# SparkFun_Pi_AVR_Programmer_HAT.net
KiCad netlist of a schematic drawn in EAGLE
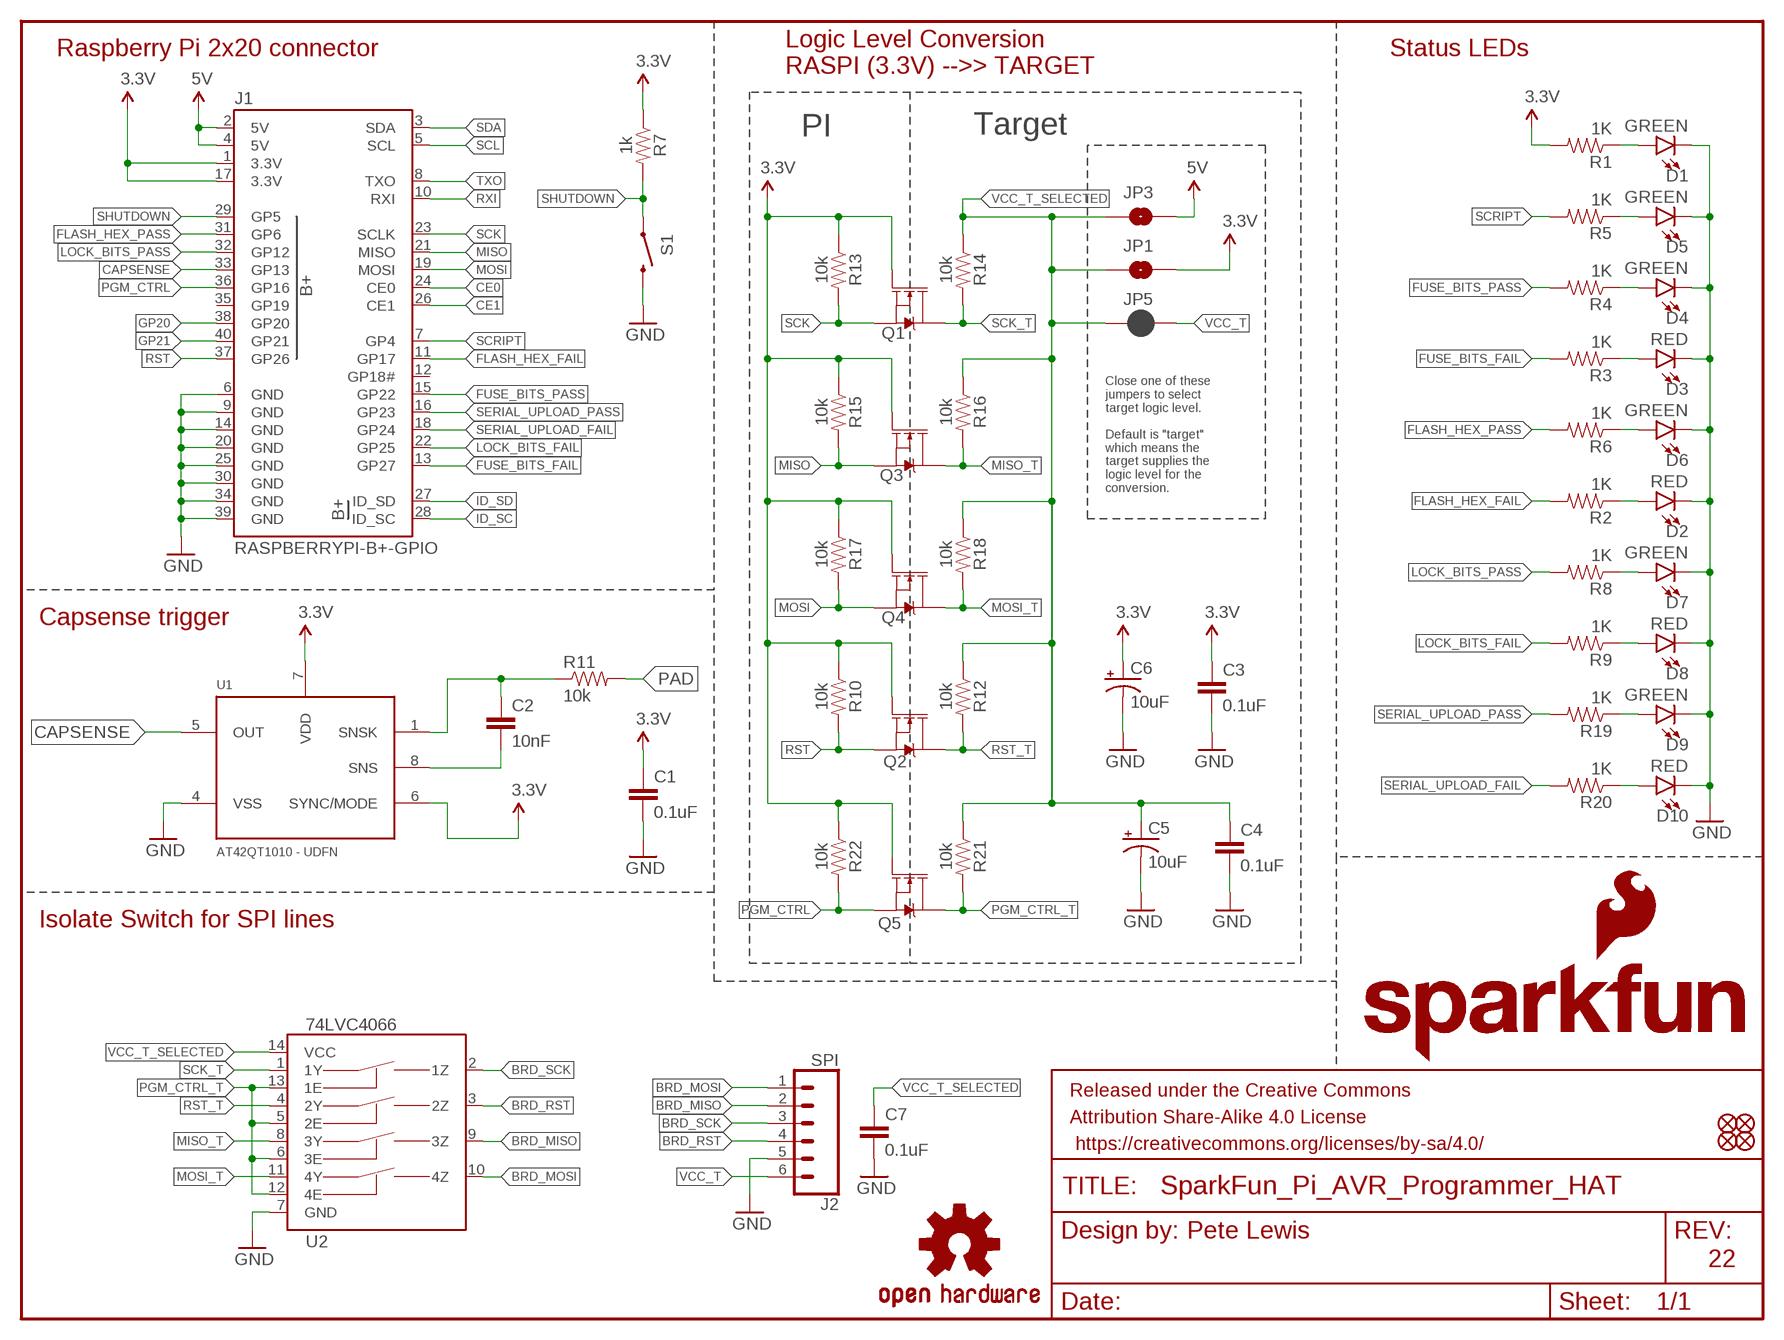
[diagram p0: schematic, sheet 1]

(export (version "E")
  (design (tool "Eeschema 10.0.6"))
  (components
    (comp (ref "C1")
      (value "0.1uF")
      (footprint "eagle-import:0603-CAP")
      (libsource (lib "eagle-import") (part "0.1UF-25V(+80/-20%)(0603)"))
    )
    (comp (ref "C2")
      (value "10nF")
      (footprint "eagle-import:0603-CAP")
      (libsource (lib "eagle-import") (part "10NF/10000PF-50V-10%(0603)"))
    )
    (comp (ref "C3")
      (value "0.1uF")
      (footprint "eagle-import:0603")
      (libsource (lib "eagle-import") (part "0.1UF-0603-25V-(+80/-20%)"))
    )
    (comp (ref "C4")
      (value "0.1uF")
      (footprint "eagle-import:0603")
      (libsource (lib "eagle-import") (part "0.1UF-0603-25V-(+80/-20%)"))
    )
    (comp (ref "C5")
      (value "10uF")
      (footprint "eagle-import:EIA3216")
      (libsource (lib "eagle-import") (part "10UF-POLAR-EIA3216-16V-10%(TANT)"))
    )
    (comp (ref "C6")
      (value "10uF")
      (footprint "eagle-import:EIA3216")
      (libsource (lib "eagle-import") (part "10UF-POLAR-EIA3216-16V-10%(TANT)"))
    )
    (comp (ref "C7")
      (value "0.1uF")
      (footprint "eagle-import:0603")
      (libsource (lib "eagle-import") (part "0.1UF-0603-25V-(+80/-20%)"))
    )
    (comp (ref "D1")
      (value "GREEN")
      (footprint "eagle-import:LED-1206")
      (libsource (lib "eagle-import") (part "LED-GREEN1206"))
    )
    (comp (ref "D2")
      (value "RED")
      (footprint "eagle-import:LED-1206")
      (libsource (lib "eagle-import") (part "LED-RED1206"))
    )
    (comp (ref "D3")
      (value "RED")
      (footprint "eagle-import:LED-1206")
      (libsource (lib "eagle-import") (part "LED-RED1206"))
    )
    (comp (ref "D4")
      (value "GREEN")
      (footprint "eagle-import:LED-1206")
      (libsource (lib "eagle-import") (part "LED-GREEN1206"))
    )
    (comp (ref "D5")
      (value "GREEN")
      (footprint "eagle-import:LED-1206")
      (libsource (lib "eagle-import") (part "LED-GREEN1206"))
    )
    (comp (ref "D6")
      (value "GREEN")
      (footprint "eagle-import:LED-1206")
      (libsource (lib "eagle-import") (part "LED-GREEN1206"))
    )
    (comp (ref "D7")
      (value "GREEN")
      (footprint "eagle-import:LED-1206")
      (libsource (lib "eagle-import") (part "LED-GREEN1206"))
    )
    (comp (ref "D8")
      (value "RED")
      (footprint "eagle-import:LED-1206")
      (libsource (lib "eagle-import") (part "LED-RED1206"))
    )
    (comp (ref "D9")
      (value "GREEN")
      (footprint "eagle-import:LED-1206")
      (libsource (lib "eagle-import") (part "LED-GREEN1206"))
    )
    (comp (ref "D10")
      (value "RED")
      (footprint "eagle-import:LED-1206")
      (libsource (lib "eagle-import") (part "LED-RED1206"))
    )
    (comp (ref "FD1")
      (value "FIDUCIALUFIDUCIAL")
      (footprint "eagle-import:FIDUCIAL-MICRO")
      (libsource (lib "eagle-import") (part "FIDUCIALUFIDUCIAL"))
    )
    (comp (ref "FD2")
      (value "FIDUCIALUFIDUCIAL")
      (footprint "eagle-import:FIDUCIAL-MICRO")
      (libsource (lib "eagle-import") (part "FIDUCIALUFIDUCIAL"))
    )
    (comp (ref "FD3")
      (value "FIDUCIALUFIDUCIAL")
      (footprint "eagle-import:FIDUCIAL-MICRO")
      (libsource (lib "eagle-import") (part "FIDUCIALUFIDUCIAL"))
    )
    (comp (ref "FD4")
      (value "FIDUCIALUFIDUCIAL")
      (footprint "eagle-import:FIDUCIAL-MICRO")
      (libsource (lib "eagle-import") (part "FIDUCIALUFIDUCIAL"))
    )
    (comp (ref "FRAME1")
      (value "FRAME-LETTER")
      (footprint "eagle-import:CREATIVE_COMMONS")
      (libsource (lib "eagle-import") (part "FRAME-LETTER"))
    )
    (comp (ref "J1")
      (value "RASPBERRYPI-B+-GPIO")
      (footprint "eagle-import:2X20-SHROUDED")
      (libsource (lib "eagle-import") (part "RASPBERRYPI-B+-GPIO"))
    )
    (comp (ref "J2")
      (value "SPI")
      (footprint "eagle-import:1X06-SMD_RA_MALE")
      (libsource (lib "eagle-import") (part "CONN_06SMD"))
    )
    (comp (ref "JP1")
      (value "JUMPER-SMT_2_NO_SILK")
      (footprint "eagle-import:SMT-JUMPER_2_NO_SILK")
      (libsource (lib "eagle-import") (part "JUMPER-SMT_2_NO_SILK"))
    )
    (comp (ref "JP3")
      (value "JUMPER-SMT_2_NO_SILK")
      (footprint "eagle-import:SMT-JUMPER_2_NO_SILK")
      (libsource (lib "eagle-import") (part "JUMPER-SMT_2_NO_SILK"))
    )
    (comp (ref "JP5")
      (value "JUMPER-SMT_2_NC_PASTE_SILK")
      (footprint "eagle-import:SMT-JUMPER_2_NC_PASTE_SILK")
      (libsource (lib "eagle-import") (part "JUMPER-SMT_2_NC_PASTE_SILK"))
    )
    (comp (ref "LOGO1")
      (value "SFE_LOGO_FLAME.2_INCH")
      (footprint "eagle-import:SFE_LOGO_FLAME_.2")
      (libsource (lib "eagle-import") (part "SFE_LOGO_FLAME.2_INCH"))
    )
    (comp (ref "LOGO2")
      (value "OSHW-LOGOL")
      (footprint "eagle-import:OSHW-LOGO-L")
      (libsource (lib "eagle-import") (part "OSHW-LOGOL"))
    )
    (comp (ref "LOGO3")
      (value "SFE_LOGO_NAME.6_INCH")
      (footprint "eagle-import:SFE_LOGO_NAME_.6")
      (libsource (lib "eagle-import") (part "SFE_LOGO_NAME.6_INCH"))
    )
    (comp (ref "Q1")
      (value "220mA/50V/3.5Ω")
      (footprint "eagle-import:SOT23-3")
      (libsource (lib "eagle-import") (part "MOSFET-NCH-BSS138"))
    )
    (comp (ref "Q2")
      (value "220mA/50V/3.5Ω")
      (footprint "eagle-import:SOT23-3")
      (libsource (lib "eagle-import") (part "MOSFET-NCH-BSS138"))
    )
    (comp (ref "Q3")
      (value "220mA/50V/3.5Ω")
      (footprint "eagle-import:SOT23-3")
      (libsource (lib "eagle-import") (part "MOSFET-NCH-BSS138"))
    )
    (comp (ref "Q4")
      (value "220mA/50V/3.5Ω")
      (footprint "eagle-import:SOT23-3")
      (libsource (lib "eagle-import") (part "MOSFET-NCH-BSS138"))
    )
    (comp (ref "Q5")
      (value "220mA/50V/3.5Ω")
      (footprint "eagle-import:SOT23-3")
      (libsource (lib "eagle-import") (part "MOSFET-NCH-BSS138"))
    )
    (comp (ref "R1")
      (value "1K")
      (footprint "eagle-import:0603-RES")
      (libsource (lib "eagle-import") (part "1KOHM-1/10W-1%(0603)"))
    )
    (comp (ref "R2")
      (value "1K")
      (footprint "eagle-import:0603-RES")
      (libsource (lib "eagle-import") (part "1KOHM-1/10W-1%(0603)"))
    )
    (comp (ref "R3")
      (value "1K")
      (footprint "eagle-import:0603-RES")
      (libsource (lib "eagle-import") (part "1KOHM-1/10W-1%(0603)"))
    )
    (comp (ref "R4")
      (value "1K")
      (footprint "eagle-import:0603-RES")
      (libsource (lib "eagle-import") (part "1KOHM-1/10W-1%(0603)"))
    )
    (comp (ref "R5")
      (value "1K")
      (footprint "eagle-import:0603-RES")
      (libsource (lib "eagle-import") (part "1KOHM-1/10W-1%(0603)"))
    )
    (comp (ref "R6")
      (value "1K")
      (footprint "eagle-import:0603-RES")
      (libsource (lib "eagle-import") (part "1KOHM-1/10W-1%(0603)"))
    )
    (comp (ref "R7")
      (value "1k")
      (footprint "eagle-import:0603")
      (libsource (lib "eagle-import") (part "1KOHM-0603-1/10W-1%"))
    )
    (comp (ref "R8")
      (value "1K")
      (footprint "eagle-import:0603-RES")
      (libsource (lib "eagle-import") (part "1KOHM-1/10W-1%(0603)"))
    )
    (comp (ref "R9")
      (value "1K")
      (footprint "eagle-import:0603-RES")
      (libsource (lib "eagle-import") (part "1KOHM-1/10W-1%(0603)"))
    )
    (comp (ref "R10")
      (value "10k")
      (footprint "eagle-import:0603")
      (libsource (lib "eagle-import") (part "10KOHM-0603-1/10W-1%"))
    )
    (comp (ref "R11")
      (value "10k")
      (footprint "eagle-import:0603-RES")
      (libsource (lib "eagle-import") (part "10KOHM-1/10W-1%(0603)0603"))
    )
    (comp (ref "R12")
      (value "10k")
      (footprint "eagle-import:0603")
      (libsource (lib "eagle-import") (part "10KOHM-0603-1/10W-1%"))
    )
    (comp (ref "R13")
      (value "10k")
      (footprint "eagle-import:0603")
      (libsource (lib "eagle-import") (part "10KOHM-0603-1/10W-1%"))
    )
    (comp (ref "R14")
      (value "10k")
      (footprint "eagle-import:0603")
      (libsource (lib "eagle-import") (part "10KOHM-0603-1/10W-1%"))
    )
    (comp (ref "R15")
      (value "10k")
      (footprint "eagle-import:0603")
      (libsource (lib "eagle-import") (part "10KOHM-0603-1/10W-1%"))
    )
    (comp (ref "R16")
      (value "10k")
      (footprint "eagle-import:0603")
      (libsource (lib "eagle-import") (part "10KOHM-0603-1/10W-1%"))
    )
    (comp (ref "R17")
      (value "10k")
      (footprint "eagle-import:0603")
      (libsource (lib "eagle-import") (part "10KOHM-0603-1/10W-1%"))
    )
    (comp (ref "R18")
      (value "10k")
      (footprint "eagle-import:0603")
      (libsource (lib "eagle-import") (part "10KOHM-0603-1/10W-1%"))
    )
    (comp (ref "R19")
      (value "1K")
      (footprint "eagle-import:0603-RES")
      (libsource (lib "eagle-import") (part "1KOHM-1/10W-1%(0603)"))
    )
    (comp (ref "R20")
      (value "1K")
      (footprint "eagle-import:0603-RES")
      (libsource (lib "eagle-import") (part "1KOHM-1/10W-1%(0603)"))
    )
    (comp (ref "R21")
      (value "10k")
      (footprint "eagle-import:0603")
      (libsource (lib "eagle-import") (part "10KOHM-0603-1/10W-1%"))
    )
    (comp (ref "R22")
      (value "10k")
      (footprint "eagle-import:0603")
      (libsource (lib "eagle-import") (part "10KOHM-0603-1/10W-1%"))
    )
    (comp (ref "S1")
      (value "SWITCH-MOMENTARY-2SMD")
      (footprint "eagle-import:TACTILE-SWITCH-SMD")
      (libsource (lib "eagle-import") (part "SWITCH-MOMENTARY-2SMD"))
    )
    (comp (ref "U1")
      (value "AT42QT1010 - UDFN")
      (footprint "eagle-import:UDFN_USON_8_PAD")
      (libsource (lib "eagle-import") (part "AT42QT1010UDFN"))
    )
    (comp (ref "U2")
      (value "74LVC4066")
      (footprint "eagle-import:SO14")
      (fields (field (name "PROD_ID") "IC-13944"))
      (libsource (lib "eagle-import") (part "74LVC4066D_QUAD_BILATERAL_SWITCH"))
    )
  )
  (nets
    (net (code "1") (name "3.3V") (class "Default")
      (node (ref "C1") (pin "1") (pinfunction "1_1") (pintype "passive"))
      (node (ref "C3") (pin "1") (pinfunction "1_1") (pintype "passive"))
      (node (ref "C6") (pin "+") (pinfunction "+_+") (pintype "passive"))
      (node (ref "J1") (pin "1") (pinfunction "3.3V_1") (pintype "power_in"))
      (node (ref "J1") (pin "17") (pinfunction "3.3V_17") (pintype "power_in"))
      (node (ref "JP1") (pin "2") (pinfunction "2_2") (pintype "passive"))
      (node (ref "Q1") (pin "1") (pinfunction "G_1") (pintype "bidirectional"))
      (node (ref "Q2") (pin "1") (pinfunction "G_1") (pintype "bidirectional"))
      (node (ref "Q3") (pin "1") (pinfunction "G_1") (pintype "bidirectional"))
      (node (ref "Q4") (pin "1") (pinfunction "G_1") (pintype "bidirectional"))
      (node (ref "Q5") (pin "1") (pinfunction "G_1") (pintype "bidirectional"))
      (node (ref "R1") (pin "2") (pinfunction "2_2") (pintype "passive"))
      (node (ref "R10") (pin "1") (pinfunction "1_1") (pintype "passive"))
      (node (ref "R13") (pin "1") (pinfunction "1_1") (pintype "passive"))
      (node (ref "R15") (pin "1") (pinfunction "1_1") (pintype "passive"))
      (node (ref "R17") (pin "1") (pinfunction "1_1") (pintype "passive"))
      (node (ref "R22") (pin "1") (pinfunction "1_1") (pintype "passive"))
      (node (ref "R7") (pin "1") (pinfunction "1_1") (pintype "passive"))
      (node (ref "U1") (pin "6") (pinfunction "SYNC/MODE_6") (pintype "bidirectional"))
      (node (ref "U1") (pin "7") (pinfunction "VDD_7") (pintype "bidirectional"))
    )
    (net (code "2") (name "5V") (class "Default")
      (node (ref "J1") (pin "2") (pinfunction "5V_2") (pintype "power_in"))
      (node (ref "J1") (pin "4") (pinfunction "5V_4") (pintype "power_in"))
      (node (ref "JP3") (pin "2") (pinfunction "2_2") (pintype "passive"))
    )
    (net (code "3") (name "BRD_MISO") (class "Default")
      (node (ref "J2") (pin "2") (pinfunction "2_2") (pintype "passive"))
      (node (ref "U2") (pin "9") (pinfunction "3Z_9") (pintype "bidirectional"))
    )
    (net (code "4") (name "BRD_MOSI") (class "Default")
      (node (ref "J2") (pin "1") (pinfunction "1_1") (pintype "passive"))
      (node (ref "U2") (pin "10") (pinfunction "4Z_10") (pintype "bidirectional"))
    )
    (net (code "5") (name "BRD_RST") (class "Default")
      (node (ref "J2") (pin "4") (pinfunction "4_4") (pintype "passive"))
      (node (ref "U2") (pin "3") (pinfunction "2Z_3") (pintype "bidirectional"))
    )
    (net (code "6") (name "BRD_SCK") (class "Default")
      (node (ref "J2") (pin "3") (pinfunction "3_3") (pintype "passive"))
      (node (ref "U2") (pin "2") (pinfunction "1Z_2") (pintype "bidirectional"))
    )
    (net (code "7") (name "CAPSENSE") (class "Default")
      (node (ref "J1") (pin "33") (pinfunction "GP13_33") (pintype "bidirectional"))
      (node (ref "U1") (pin "5") (pinfunction "OUT_5") (pintype "bidirectional"))
    )
    (net (code "8") (name "CE0") (class "Default")
      (node (ref "J1") (pin "24") (pinfunction "CE0_24") (pintype "output"))
    )
    (net (code "9") (name "CE1") (class "Default")
      (node (ref "J1") (pin "26") (pinfunction "CE1_26") (pintype "output"))
    )
    (net (code "10") (name "FLASH_HEX_FAIL") (class "Default")
      (node (ref "J1") (pin "11") (pinfunction "GP17_11") (pintype "bidirectional"))
      (node (ref "R2") (pin "2") (pinfunction "2_2") (pintype "passive"))
    )
    (net (code "11") (name "FLASH_HEX_PASS") (class "Default")
      (node (ref "J1") (pin "31") (pinfunction "GP6_31") (pintype "bidirectional"))
      (node (ref "R6") (pin "2") (pinfunction "2_2") (pintype "passive"))
    )
    (net (code "12") (name "FUSE_BITS_FAIL") (class "Default")
      (node (ref "J1") (pin "13") (pinfunction "GP27_13") (pintype "bidirectional"))
      (node (ref "R3") (pin "2") (pinfunction "2_2") (pintype "passive"))
    )
    (net (code "13") (name "FUSE_BITS_PASS") (class "Default")
      (node (ref "J1") (pin "15") (pinfunction "GP22_15") (pintype "bidirectional"))
      (node (ref "R4") (pin "2") (pinfunction "2_2") (pintype "passive"))
    )
    (net (code "14") (name "GND") (class "Default")
      (node (ref "C1") (pin "2") (pinfunction "2_2") (pintype "passive"))
      (node (ref "C3") (pin "2") (pinfunction "2_2") (pintype "passive"))
      (node (ref "C4") (pin "2") (pinfunction "2_2") (pintype "passive"))
      (node (ref "C5") (pin "-") (pinfunction "-_-") (pintype "passive"))
      (node (ref "C6") (pin "-") (pinfunction "-_-") (pintype "passive"))
      (node (ref "C7") (pin "2") (pinfunction "2_2") (pintype "passive"))
      (node (ref "D1") (pin "C") (pinfunction "C_C") (pintype "passive"))
      (node (ref "D10") (pin "C") (pinfunction "C_C") (pintype "passive"))
      (node (ref "D2") (pin "C") (pinfunction "C_C") (pintype "passive"))
      (node (ref "D3") (pin "C") (pinfunction "C_C") (pintype "passive"))
      (node (ref "D4") (pin "C") (pinfunction "C_C") (pintype "passive"))
      (node (ref "D5") (pin "C") (pinfunction "C_C") (pintype "passive"))
      (node (ref "D6") (pin "C") (pinfunction "C_C") (pintype "passive"))
      (node (ref "D7") (pin "C") (pinfunction "C_C") (pintype "passive"))
      (node (ref "D8") (pin "C") (pinfunction "C_C") (pintype "passive"))
      (node (ref "D9") (pin "C") (pinfunction "C_C") (pintype "passive"))
      (node (ref "J1") (pin "14") (pinfunction "GND_14") (pintype "power_in"))
      (node (ref "J1") (pin "20") (pinfunction "GND_20") (pintype "power_in"))
      (node (ref "J1") (pin "25") (pinfunction "GND_25") (pintype "power_in"))
      (node (ref "J1") (pin "30") (pinfunction "GND_30") (pintype "power_in"))
      (node (ref "J1") (pin "34") (pinfunction "GND_34") (pintype "power_in"))
      (node (ref "J1") (pin "39") (pinfunction "GND_39") (pintype "power_in"))
      (node (ref "J1") (pin "6") (pinfunction "GND_6") (pintype "power_in"))
      (node (ref "J1") (pin "9") (pinfunction "GND_9") (pintype "power_in"))
      (node (ref "J2") (pin "5") (pinfunction "5_5") (pintype "passive"))
      (node (ref "S1") (pin "3") (pinfunction "2_3") (pintype "passive"))
      (node (ref "U1") (pin "4") (pinfunction "VSS_4") (pintype "bidirectional"))
      (node (ref "U2") (pin "7") (pinfunction "GND_7") (pintype "bidirectional"))
    )
    (net (code "15") (name "GP20") (class "Default")
      (node (ref "J1") (pin "38") (pinfunction "GP20_38") (pintype "bidirectional"))
    )
    (net (code "16") (name "GP21") (class "Default")
      (node (ref "J1") (pin "40") (pinfunction "GP21_40") (pintype "bidirectional"))
    )
    (net (code "17") (name "ID_SC") (class "Default")
      (node (ref "J1") (pin "28") (pinfunction "ID_SC_28") (pintype "bidirectional"))
    )
    (net (code "18") (name "ID_SD") (class "Default")
      (node (ref "J1") (pin "27") (pinfunction "ID_SD_27") (pintype "bidirectional"))
    )
    (net (code "19") (name "LOCK_BITS_FAIL") (class "Default")
      (node (ref "J1") (pin "22") (pinfunction "GP25_22") (pintype "bidirectional"))
      (node (ref "R9") (pin "2") (pinfunction "2_2") (pintype "passive"))
    )
    (net (code "20") (name "LOCK_BITS_PASS") (class "Default")
      (node (ref "J1") (pin "32") (pinfunction "GP12_32") (pintype "bidirectional"))
      (node (ref "R8") (pin "2") (pinfunction "2_2") (pintype "passive"))
    )
    (net (code "21") (name "MISO") (class "Default")
      (node (ref "J1") (pin "21") (pinfunction "MISO_21") (pintype "input"))
      (node (ref "Q3") (pin "2") (pinfunction "S_2") (pintype "bidirectional"))
      (node (ref "R15") (pin "2") (pinfunction "2_2") (pintype "passive"))
    )
    (net (code "22") (name "MISO_T") (class "Default")
      (node (ref "Q3") (pin "3") (pinfunction "D_3") (pintype "bidirectional"))
      (node (ref "R16") (pin "2") (pinfunction "2_2") (pintype "passive"))
      (node (ref "U2") (pin "8") (pinfunction "3Y_8") (pintype "bidirectional"))
    )
    (net (code "23") (name "MOSI") (class "Default")
      (node (ref "J1") (pin "19") (pinfunction "MOSI_19") (pintype "output"))
      (node (ref "Q4") (pin "2") (pinfunction "S_2") (pintype "bidirectional"))
      (node (ref "R17") (pin "2") (pinfunction "2_2") (pintype "passive"))
    )
    (net (code "24") (name "MOSI_T") (class "Default")
      (node (ref "Q4") (pin "3") (pinfunction "D_3") (pintype "bidirectional"))
      (node (ref "R18") (pin "2") (pinfunction "2_2") (pintype "passive"))
      (node (ref "U2") (pin "11") (pinfunction "4Y_11") (pintype "bidirectional"))
    )
    (net (code "25") (name "Net-(D1-PadA)") (class "Default")
      (node (ref "D1") (pin "A") (pinfunction "A_A") (pintype "passive"))
      (node (ref "R1") (pin "1") (pinfunction "1_1") (pintype "passive"))
    )
    (net (code "26") (name "Net-(D2-PadA)") (class "Default")
      (node (ref "D2") (pin "A") (pinfunction "A_A") (pintype "passive"))
      (node (ref "R2") (pin "1") (pinfunction "1_1") (pintype "passive"))
    )
    (net (code "27") (name "Net-(D3-PadA)") (class "Default")
      (node (ref "D3") (pin "A") (pinfunction "A_A") (pintype "passive"))
      (node (ref "R3") (pin "1") (pinfunction "1_1") (pintype "passive"))
    )
    (net (code "28") (name "Net-(D4-PadA)") (class "Default")
      (node (ref "D4") (pin "A") (pinfunction "A_A") (pintype "passive"))
      (node (ref "R4") (pin "1") (pinfunction "1_1") (pintype "passive"))
    )
    (net (code "29") (name "Net-(D5-PadA)") (class "Default")
      (node (ref "D5") (pin "A") (pinfunction "A_A") (pintype "passive"))
      (node (ref "R5") (pin "1") (pinfunction "1_1") (pintype "passive"))
    )
    (net (code "30") (name "Net-(D6-PadA)") (class "Default")
      (node (ref "D6") (pin "A") (pinfunction "A_A") (pintype "passive"))
      (node (ref "R6") (pin "1") (pinfunction "1_1") (pintype "passive"))
    )
    (net (code "31") (name "Net-(D7-PadA)") (class "Default")
      (node (ref "D7") (pin "A") (pinfunction "A_A") (pintype "passive"))
      (node (ref "R8") (pin "1") (pinfunction "1_1") (pintype "passive"))
    )
    (net (code "32") (name "Net-(D8-PadA)") (class "Default")
      (node (ref "D8") (pin "A") (pinfunction "A_A") (pintype "passive"))
      (node (ref "R9") (pin "1") (pinfunction "1_1") (pintype "passive"))
    )
    (net (code "33") (name "Net-(D9-PadA)") (class "Default")
      (node (ref "D9") (pin "A") (pinfunction "A_A") (pintype "passive"))
      (node (ref "R19") (pin "1") (pinfunction "1_1") (pintype "passive"))
    )
    (net (code "34") (name "Net-(D10-PadA)") (class "Default")
      (node (ref "D10") (pin "A") (pinfunction "A_A") (pintype "passive"))
      (node (ref "R20") (pin "1") (pinfunction "1_1") (pintype "passive"))
    )
    (net (code "35") (name "Net-(U1-SNS)") (class "Default")
      (node (ref "C2") (pin "2") (pinfunction "2_2") (pintype "passive"))
      (node (ref "U1") (pin "8") (pinfunction "SNS_8") (pintype "bidirectional"))
    )
    (net (code "36") (name "Net-(U1-SNSK)") (class "Default")
      (node (ref "C2") (pin "1") (pinfunction "1_1") (pintype "passive"))
      (node (ref "R11") (pin "1") (pinfunction "1_1") (pintype "passive"))
      (node (ref "U1") (pin "1") (pinfunction "SNSK_1") (pintype "bidirectional"))
    )
    (net (code "37") (name "PAD") (class "Default")
      (node (ref "R11") (pin "2") (pinfunction "2_2") (pintype "passive"))
    )
    (net (code "38") (name "PGM_CTRL") (class "Default")
      (node (ref "J1") (pin "36") (pinfunction "GP16_36") (pintype "bidirectional"))
      (node (ref "Q5") (pin "2") (pinfunction "S_2") (pintype "bidirectional"))
      (node (ref "R22") (pin "2") (pinfunction "2_2") (pintype "passive"))
    )
    (net (code "39") (name "PGM_CTRL_T") (class "Default")
      (node (ref "Q5") (pin "3") (pinfunction "D_3") (pintype "bidirectional"))
      (node (ref "R21") (pin "2") (pinfunction "2_2") (pintype "passive"))
      (node (ref "U2") (pin "12") (pinfunction "4E_12") (pintype "bidirectional"))
      (node (ref "U2") (pin "13") (pinfunction "1E_13") (pintype "bidirectional"))
      (node (ref "U2") (pin "5") (pinfunction "2E_5") (pintype "bidirectional"))
      (node (ref "U2") (pin "6") (pinfunction "3E_6") (pintype "bidirectional"))
    )
    (net (code "40") (name "RST") (class "Default")
      (node (ref "J1") (pin "37") (pinfunction "GP26_37") (pintype "bidirectional"))
      (node (ref "Q2") (pin "2") (pinfunction "S_2") (pintype "bidirectional"))
      (node (ref "R10") (pin "2") (pinfunction "2_2") (pintype "passive"))
    )
    (net (code "41") (name "RST_T") (class "Default")
      (node (ref "Q2") (pin "3") (pinfunction "D_3") (pintype "bidirectional"))
      (node (ref "R12") (pin "2") (pinfunction "2_2") (pintype "passive"))
      (node (ref "U2") (pin "4") (pinfunction "2Y_4") (pintype "bidirectional"))
    )
    (net (code "42") (name "RXI") (class "Default")
      (node (ref "J1") (pin "10") (pinfunction "RXI_10") (pintype "input"))
    )
    (net (code "43") (name "SCK") (class "Default")
      (node (ref "J1") (pin "23") (pinfunction "SCLK_23") (pintype "output"))
      (node (ref "Q1") (pin "2") (pinfunction "S_2") (pintype "bidirectional"))
      (node (ref "R13") (pin "2") (pinfunction "2_2") (pintype "passive"))
    )
    (net (code "44") (name "SCK_T") (class "Default")
      (node (ref "Q1") (pin "3") (pinfunction "D_3") (pintype "bidirectional"))
      (node (ref "R14") (pin "2") (pinfunction "2_2") (pintype "passive"))
      (node (ref "U2") (pin "1") (pinfunction "1Y_1") (pintype "bidirectional"))
    )
    (net (code "45") (name "SCL") (class "Default")
      (node (ref "J1") (pin "5") (pinfunction "SCL_5") (pintype "bidirectional"))
    )
    (net (code "46") (name "SCRIPT") (class "Default")
      (node (ref "J1") (pin "7") (pinfunction "GP4_7") (pintype "bidirectional"))
      (node (ref "R5") (pin "2") (pinfunction "2_2") (pintype "passive"))
    )
    (net (code "47") (name "SDA") (class "Default")
      (node (ref "J1") (pin "3") (pinfunction "SDA_3") (pintype "bidirectional"))
    )
    (net (code "48") (name "SERIAL_UPLOAD_FAIL") (class "Default")
      (node (ref "J1") (pin "18") (pinfunction "GP24_18") (pintype "bidirectional"))
      (node (ref "R20") (pin "2") (pinfunction "2_2") (pintype "passive"))
    )
    (net (code "49") (name "SERIAL_UPLOAD_PASS") (class "Default")
      (node (ref "J1") (pin "16") (pinfunction "GP23_16") (pintype "bidirectional"))
      (node (ref "R19") (pin "2") (pinfunction "2_2") (pintype "passive"))
    )
    (net (code "50") (name "SHUTDOWN") (class "Default")
      (node (ref "J1") (pin "29") (pinfunction "GP5_29") (pintype "bidirectional"))
      (node (ref "R7") (pin "2") (pinfunction "2_2") (pintype "passive"))
      (node (ref "S1") (pin "1") (pinfunction "1_1") (pintype "passive"))
    )
    (net (code "51") (name "TXO") (class "Default")
      (node (ref "J1") (pin "8") (pinfunction "TXO_8") (pintype "output"))
    )
    (net (code "52") (name "VCC_T") (class "Default")
      (node (ref "J2") (pin "6") (pinfunction "6_6") (pintype "passive"))
      (node (ref "JP5") (pin "2") (pinfunction "2_2") (pintype "passive"))
    )
    (net (code "53") (name "VCC_T_SELECTED") (class "Default")
      (node (ref "C4") (pin "1") (pinfunction "1_1") (pintype "passive"))
      (node (ref "C5") (pin "+") (pinfunction "+_+") (pintype "passive"))
      (node (ref "C7") (pin "1") (pinfunction "1_1") (pintype "passive"))
      (node (ref "JP1") (pin "1") (pinfunction "1_1") (pintype "passive"))
      (node (ref "JP3") (pin "1") (pinfunction "1_1") (pintype "passive"))
      (node (ref "JP5") (pin "1") (pinfunction "1_1") (pintype "passive"))
      (node (ref "R12") (pin "1") (pinfunction "1_1") (pintype "passive"))
      (node (ref "R14") (pin "1") (pinfunction "1_1") (pintype "passive"))
      (node (ref "R16") (pin "1") (pinfunction "1_1") (pintype "passive"))
      (node (ref "R18") (pin "1") (pinfunction "1_1") (pintype "passive"))
      (node (ref "R21") (pin "1") (pinfunction "1_1") (pintype "passive"))
      (node (ref "U2") (pin "14") (pinfunction "VCC_14") (pintype "bidirectional"))
    )
    (net (code "54") (name "unconnected-(J1-GP18#-Pad12)") (class "Default")
      (node (ref "J1") (pin "12") (pinfunction "GP18#_12") (pintype "bidirectional"))
    )
    (net (code "55") (name "unconnected-(J1-GP19-Pad35)") (class "Default")
      (node (ref "J1") (pin "35") (pinfunction "GP19_35") (pintype "bidirectional"))
    )
  )
)
